# sch_LIMA_Driver.net
KiCad netlist of a schematic drawn in Altium Designer
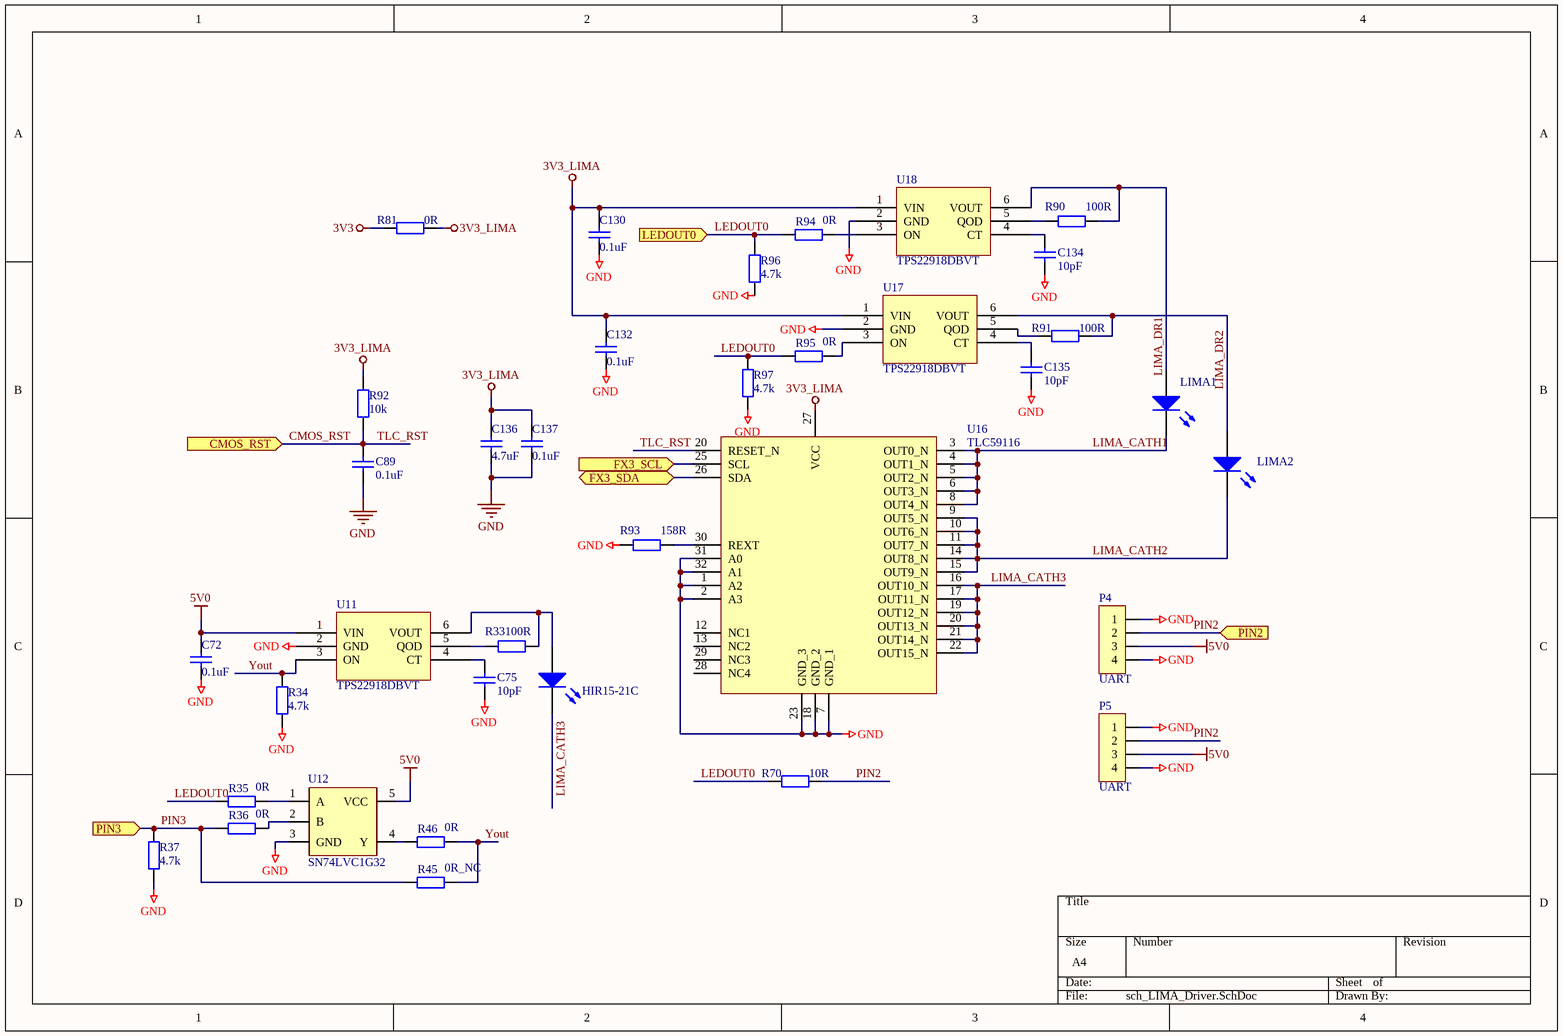
[diagram p0: sch_LIMA_Driver.SchDoc]

(export (version "E")
  (design (tool "Eeschema 10.0.6"))
  (components
    (comp (ref "C72")
      (value "0.1uF")
      (description "Capacitor")
      (fields (field (name "PUBLISHER") "Altium Limited"))
      (libsource (lib "Miscellaneous Devices") (part "Cap"))
    )
    (comp (ref "C75")
      (value "10pF")
      (footprint "0603C_N")
      (description "Capacitor")
      (fields (field (name "PUBLISHER") "Altium Limited"))
      (libsource (lib "Miscellaneous Devices") (part "Cap"))
    )
    (comp (ref "C89")
      (value "0.1uF")
      (footprint "0402C_L")
      (description "Capacitor")
      (fields (field (name "PUBLISHER") "Altium Limited"))
      (libsource (lib "Miscellaneous Devices") (part "Cap"))
    )
    (comp (ref "C130")
      (value "0.1uF")
      (footprint "0402C_L")
      (description "Capacitor")
      (fields (field (name "PUBLISHER") "Altium Limited"))
      (libsource (lib "Miscellaneous Devices") (part "Cap"))
    )
    (comp (ref "C132")
      (value "0.1uF")
      (footprint "0402C_L")
      (description "Capacitor")
      (fields (field (name "PUBLISHER") "Altium Limited"))
      (libsource (lib "Miscellaneous Devices") (part "Cap"))
    )
    (comp (ref "C134")
      (value "10pF")
      (footprint "0402C_L")
      (description "Capacitor")
      (fields (field (name "PUBLISHER") "Altium Limited"))
      (libsource (lib "Miscellaneous Devices") (part "Cap"))
    )
    (comp (ref "C135")
      (value "10pF")
      (footprint "0402C_L")
      (description "Capacitor")
      (fields (field (name "PUBLISHER") "Altium Limited"))
      (libsource (lib "Miscellaneous Devices") (part "Cap"))
    )
    (comp (ref "C136")
      (value "4.7uF")
      (description "Capacitor")
      (fields (field (name "PUBLISHER") "Altium Limited"))
      (libsource (lib "Miscellaneous Devices") (part "Cap"))
    )
    (comp (ref "C137")
      (value "0.1uF")
      (footprint "0402C")
      (description "Capacitor")
      (fields (field (name "PUBLISHER") "Altium Limited"))
      (libsource (lib "Miscellaneous Devices") (part "Cap"))
    )
    (comp (ref "HIR15-21C")
      (value "LIMA")
      (footprint "1206R")
      (description "发光二级管")
      (libsource (lib "TXW") (part "LED"))
    )
    (comp (ref "LIMA1") (value "LIMA") (description "发光二级管") (libsource (lib "TXW") (part "LED")))
    (comp (ref "LIMA2") (value "LIMA") (description "发光二级管") (libsource (lib "TXW") (part "LED")))
    (comp (ref "P4")
      (value "UART")
      (footprint "WAFER4_P1.25L6.25W3.4H4.3")
      (libsource (lib "KS_Drive") (part "CON4"))
    )
    (comp (ref "P5")
      (value "UART")
      (footprint "WAFER4_P1.25L6.25W3.4H4.3")
      (libsource (lib "KS_Drive") (part "CON4"))
    )
    (comp (ref "R33")
      (value "100R")
      (footprint "0603R_N")
      (description "Resistor")
      (fields (field (name "PUBLISHER") "Altium Limited"))
      (libsource (lib "SZG") (part "Resistor"))
    )
    (comp (ref "R34")
      (value "4.7k")
      (footprint "0603R_N")
      (description "Resistor")
      (fields (field (name "PUBLISHER") "Altium Limited"))
      (libsource (lib "") (part "Resistor_1"))
    )
    (comp (ref "R35")
      (value "0R")
      (footprint "0603R_N")
      (description "Resistor")
      (fields (field (name "PUBLISHER") "Altium Limited"))
      (libsource (lib "SZG") (part "Resistor"))
    )
    (comp (ref "R36")
      (value "0R")
      (footprint "0603R_N")
      (description "Resistor")
      (fields (field (name "PUBLISHER") "Altium Limited"))
      (libsource (lib "SZG") (part "Resistor"))
    )
    (comp (ref "R37")
      (value "4.7k")
      (footprint "0603R_N")
      (description "Resistor")
      (fields (field (name "PUBLISHER") "Altium Limited"))
      (libsource (lib "") (part "Resistor_1"))
    )
    (comp (ref "R45")
      (value "0R_NC")
      (footprint "0603R_N")
      (description "Resistor")
      (fields (field (name "PUBLISHER") "Altium Limited"))
      (libsource (lib "SZG") (part "Resistor"))
    )
    (comp (ref "R46")
      (value "0R")
      (footprint "0603R_N")
      (description "Resistor")
      (fields (field (name "PUBLISHER") "Altium Limited"))
      (libsource (lib "SZG") (part "Resistor"))
    )
    (comp (ref "R70")
      (value "10R")
      (footprint "0402R")
      (description "Resistor")
      (fields (field (name "PUBLISHER") "Altium Limited"))
      (libsource (lib "") (part "Resistor_2"))
    )
    (comp (ref "R81")
      (value "0R")
      (footprint "0402R")
      (description "Resistor")
      (fields (field (name "PUBLISHER") "Altium Limited"))
      (libsource (lib "") (part "Resistor_2"))
    )
    (comp (ref "R90")
      (value "100R")
      (footprint "0402R")
      (description "Resistor")
      (fields (field (name "PUBLISHER") "Altium Limited"))
      (libsource (lib "SZG") (part "Resistor"))
    )
    (comp (ref "R91")
      (value "100R")
      (footprint "0402R")
      (description "Resistor")
      (fields (field (name "PUBLISHER") "Altium Limited"))
      (libsource (lib "SZG") (part "Resistor"))
    )
    (comp (ref "R92")
      (value "10k")
      (footprint "0402R")
      (description "Resistor")
      (fields (field (name "PUBLISHER") "Altium Limited"))
      (libsource (lib "") (part "Resistor_3"))
    )
    (comp (ref "R93")
      (value "158R")
      (footprint "0402R")
      (description "Resistor")
      (fields (field (name "PUBLISHER") "Altium Limited"))
      (libsource (lib "SZG") (part "Resistor"))
    )
    (comp (ref "R94")
      (value "0R")
      (footprint "0402R")
      (description "Resistor")
      (fields (field (name "PUBLISHER") "Altium Limited"))
      (libsource (lib "SZG") (part "Resistor"))
    )
    (comp (ref "R95")
      (value "0R")
      (footprint "0402R")
      (description "Resistor")
      (fields (field (name "PUBLISHER") "Altium Limited"))
      (libsource (lib "SZG") (part "Resistor"))
    )
    (comp (ref "R96")
      (value "4.7k")
      (footprint "0402R")
      (description "Resistor")
      (fields (field (name "PUBLISHER") "Altium Limited"))
      (libsource (lib "") (part "Resistor_1"))
    )
    (comp (ref "R97")
      (value "4.7k")
      (footprint "0402R")
      (description "Resistor")
      (fields (field (name "PUBLISHER") "Altium Limited"))
      (libsource (lib "") (part "Resistor_1"))
    )
    (comp (ref "U11")
      (value "TPS22918DBVT")
      (footprint "SOT23-6_P0.95X2.4_L3W4.2H1.1")
      (libsource (lib "SZG") (part "TPS22918DBVT"))
    )
    (comp (ref "U12")
      (value "SN74LVC1G32")
      (footprint "SOT23-5_P0.95X2.4_L3W4.2H1.1")
      (libsource (lib "SZG") (part "SN74LVC1G32"))
    )
    (comp (ref "U16") (value "TLC59116") (libsource (lib "SZG") (part "TLC59116")))
    (comp (ref "U17") (value "TPS22918DBVT") (libsource (lib "SZG") (part "TPS22918DBVT")))
    (comp (ref "U18") (value "TPS22918DBVT") (libsource (lib "SZG") (part "TPS22918DBVT")))
  )
  (nets
    (net (code "1") (name "/CMOS_RST") (class "Default")
      (node (ref "C89") (pin "2") (pinfunction "2_2") (pintype "passive"))
      (node (ref "R92") (pin "2") (pinfunction "2_2") (pintype "passive"))
      (node (ref "U16") (pin "20") (pinfunction "RESET_N_20") (pintype "passive"))
    )
    (net (code "2") (name "/FX3_SCL") (class "Default")
      (node (ref "U16") (pin "25") (pinfunction "SCL_25") (pintype "passive"))
    )
    (net (code "3") (name "/FX3_SDA") (class "Default")
      (node (ref "U16") (pin "26") (pinfunction "SDA_26") (pintype "passive"))
    )
    (net (code "4") (name "/LEDOUT0") (class "Default")
      (node (ref "R35") (pin "2") (pinfunction "2_2") (pintype "passive"))
      (node (ref "R70") (pin "1") (pinfunction "1_1") (pintype "passive"))
      (node (ref "R94") (pin "2") (pinfunction "2_2") (pintype "passive"))
      (node (ref "R95") (pin "2") (pinfunction "2_2") (pintype "passive"))
      (node (ref "R96") (pin "2") (pinfunction "2_2") (pintype "passive"))
      (node (ref "R97") (pin "2") (pinfunction "2_2") (pintype "passive"))
    )
    (net (code "5") (name "/LIMA_CATH1") (class "Default")
      (node (ref "LIMA1") (pin "2") (pinfunction "K_2") (pintype "passive"))
      (node (ref "U16") (pin "3") (pinfunction "OUT0_N_3") (pintype "passive"))
      (node (ref "U16") (pin "4") (pinfunction "OUT1_N_4") (pintype "passive"))
      (node (ref "U16") (pin "5") (pinfunction "OUT2_N_5") (pintype "passive"))
      (node (ref "U16") (pin "6") (pinfunction "OUT3_N_6") (pintype "passive"))
      (node (ref "U16") (pin "8") (pinfunction "OUT4_N_8") (pintype "passive"))
    )
    (net (code "6") (name "/LIMA_CATH2") (class "Default")
      (node (ref "LIMA2") (pin "2") (pinfunction "K_2") (pintype "passive"))
      (node (ref "U16") (pin "10") (pinfunction "OUT6_N_10") (pintype "passive"))
      (node (ref "U16") (pin "11") (pinfunction "OUT7_N_11") (pintype "passive"))
      (node (ref "U16") (pin "14") (pinfunction "OUT8_N_14") (pintype "passive"))
      (node (ref "U16") (pin "15") (pinfunction "OUT9_N_15") (pintype "passive"))
      (node (ref "U16") (pin "9") (pinfunction "OUT5_N_9") (pintype "passive"))
    )
    (net (code "7") (name "/LIMA_CATH3") (class "Default")
      (node (ref "HIR15-21C") (pin "2") (pinfunction "K_2") (pintype "passive"))
      (node (ref "U16") (pin "16") (pinfunction "OUT10_N_16") (pintype "passive"))
      (node (ref "U16") (pin "17") (pinfunction "OUT11_N_17") (pintype "passive"))
      (node (ref "U16") (pin "19") (pinfunction "OUT12_N_19") (pintype "passive"))
      (node (ref "U16") (pin "20") (pinfunction "OUT13_N_20") (pintype "passive"))
      (node (ref "U16") (pin "21") (pinfunction "OUT14_N_21") (pintype "passive"))
      (node (ref "U16") (pin "22") (pinfunction "OUT15_N_22") (pintype "passive"))
    )
    (net (code "9") (name "/LIMA_DR2") (class "Default")
      (node (ref "LIMA2") (pin "1") (pinfunction "A_1") (pintype "passive"))
      (node (ref "R91") (pin "1") (pinfunction "1_1") (pintype "passive"))
      (node (ref "U17") (pin "6") (pinfunction "VOUT_6") (pintype "passive"))
    )
    (net (code "10") (name "/PIN2") (class "Default")
      (node (ref "P4") (pin "2") (pinfunction "2_2") (pintype "passive"))
      (node (ref "P5") (pin "2") (pinfunction "2_2") (pintype "passive"))
      (node (ref "R70") (pin "2") (pinfunction "2_2") (pintype "passive"))
    )
    (net (code "11") (name "/PIN3") (class "Default")
      (node (ref "R36") (pin "2") (pinfunction "2_2") (pintype "passive"))
      (node (ref "R37") (pin "2") (pinfunction "2_2") (pintype "passive"))
      (node (ref "R45") (pin "2") (pinfunction "2_2") (pintype "passive"))
    )
    (net (code "12") (name "/Yout") (class "Default")
      (node (ref "R34") (pin "2") (pinfunction "2_2") (pintype "passive"))
      (node (ref "R45") (pin "1") (pinfunction "1_1") (pintype "passive"))
      (node (ref "R46") (pin "1") (pinfunction "1_1") (pintype "passive"))
      (node (ref "U11") (pin "3") (pinfunction "ON_3") (pintype "passive"))
    )
    (net (code "13") (name "3V3") (class "Default")
      (node (ref "R81") (pin "1") (pinfunction "1_1") (pintype "passive"))
    )
    (net (code "14") (name "3V3_LIMA") (class "Default")
      (node (ref "C130") (pin "2") (pinfunction "2_2") (pintype "passive"))
      (node (ref "C132") (pin "2") (pinfunction "2_2") (pintype "passive"))
      (node (ref "C136") (pin "2") (pinfunction "2_2") (pintype "passive"))
      (node (ref "C137") (pin "2") (pinfunction "2_2") (pintype "passive"))
      (node (ref "R81") (pin "2") (pinfunction "2_2") (pintype "passive"))
      (node (ref "R92") (pin "1") (pinfunction "1_1") (pintype "passive"))
      (node (ref "U16") (pin "27") (pinfunction "VCC_27") (pintype "passive"))
      (node (ref "U17") (pin "1") (pinfunction "VIN_1") (pintype "passive"))
      (node (ref "U18") (pin "1") (pinfunction "VIN_1") (pintype "passive"))
    )
    (net (code "15") (name "5V0") (class "Default")
      (node (ref "C72") (pin "2") (pinfunction "2_2") (pintype "passive"))
      (node (ref "P4") (pin "3") (pinfunction "3_3") (pintype "passive"))
      (node (ref "P5") (pin "3") (pinfunction "3_3") (pintype "passive"))
      (node (ref "U11") (pin "1") (pinfunction "VIN_1") (pintype "passive"))
      (node (ref "U12") (pin "5") (pinfunction "VCC_5") (pintype "passive"))
    )
    (net (code "16") (name "GND") (class "Default")
      (node (ref "C130") (pin "1") (pinfunction "1_1") (pintype "passive"))
      (node (ref "C132") (pin "1") (pinfunction "1_1") (pintype "passive"))
      (node (ref "C134") (pin "1") (pinfunction "1_1") (pintype "passive"))
      (node (ref "C135") (pin "1") (pinfunction "1_1") (pintype "passive"))
      (node (ref "C136") (pin "1") (pinfunction "1_1") (pintype "passive"))
      (node (ref "C137") (pin "1") (pinfunction "1_1") (pintype "passive"))
      (node (ref "C72") (pin "1") (pinfunction "1_1") (pintype "passive"))
      (node (ref "C75") (pin "1") (pinfunction "1_1") (pintype "passive"))
      (node (ref "C89") (pin "1") (pinfunction "1_1") (pintype "passive"))
      (node (ref "P4") (pin "1") (pinfunction "1_1") (pintype "passive"))
      (node (ref "P4") (pin "4") (pinfunction "4_4") (pintype "passive"))
      (node (ref "P5") (pin "1") (pinfunction "1_1") (pintype "passive"))
      (node (ref "P5") (pin "4") (pinfunction "4_4") (pintype "passive"))
      (node (ref "R34") (pin "1") (pinfunction "1_1") (pintype "passive"))
      (node (ref "R37") (pin "1") (pinfunction "1_1") (pintype "passive"))
      (node (ref "R93") (pin "2") (pinfunction "2_2") (pintype "passive"))
      (node (ref "R96") (pin "1") (pinfunction "1_1") (pintype "passive"))
      (node (ref "R97") (pin "1") (pinfunction "1_1") (pintype "passive"))
      (node (ref "U11") (pin "2") (pinfunction "GND_2") (pintype "passive"))
      (node (ref "U12") (pin "3") (pinfunction "GND_3") (pintype "passive"))
      (node (ref "U16") (pin "1") (pinfunction "A2_1") (pintype "passive"))
      (node (ref "U16") (pin "18") (pinfunction "GND_2_18") (pintype "passive"))
      (node (ref "U16") (pin "2") (pinfunction "A3_2") (pintype "passive"))
      (node (ref "U16") (pin "23") (pinfunction "GND_3_23") (pintype "passive"))
      (node (ref "U16") (pin "31") (pinfunction "A0_31") (pintype "passive"))
      (node (ref "U16") (pin "32") (pinfunction "A1_32") (pintype "passive"))
      (node (ref "U16") (pin "7") (pinfunction "GND_1_7") (pintype "passive"))
      (node (ref "U17") (pin "2") (pinfunction "GND_2") (pintype "passive"))
      (node (ref "U18") (pin "2") (pinfunction "GND_2") (pintype "passive"))
    )
    (net (code "17") (name "Net-(HIR15-21C-A)") (class "Default")
      (node (ref "HIR15-21C") (pin "1") (pinfunction "A_1") (pintype "passive"))
      (node (ref "R33") (pin "1") (pinfunction "1_1") (pintype "passive"))
      (node (ref "U11") (pin "6") (pinfunction "VOUT_6") (pintype "passive"))
    )
    (net (code "18") (name "Net-(LIMA1-A)") (class "Default")
      (node (ref "LIMA1") (pin "1") (pinfunction "A_1") (pintype "passive"))
      (node (ref "R90") (pin "1") (pinfunction "1_1") (pintype "passive"))
      (node (ref "U18") (pin "6") (pinfunction "VOUT_6") (pintype "passive"))
    )
    (net (code "19") (name "Net-(U11-CT)") (class "Default")
      (node (ref "C75") (pin "2") (pinfunction "2_2") (pintype "passive"))
      (node (ref "U11") (pin "4") (pinfunction "CT_4") (pintype "passive"))
    )
    (net (code "20") (name "Net-(U11-QOD)") (class "Default")
      (node (ref "R33") (pin "2") (pinfunction "2_2") (pintype "passive"))
      (node (ref "U11") (pin "5") (pinfunction "QOD_5") (pintype "passive"))
    )
    (net (code "21") (name "Net-(U12-A)") (class "Default")
      (node (ref "R35") (pin "1") (pinfunction "1_1") (pintype "passive"))
      (node (ref "U12") (pin "1") (pinfunction "A_1") (pintype "passive"))
    )
    (net (code "22") (name "Net-(U12-B)") (class "Default")
      (node (ref "R36") (pin "1") (pinfunction "1_1") (pintype "passive"))
      (node (ref "U12") (pin "2") (pinfunction "B_2") (pintype "passive"))
    )
    (net (code "23") (name "Net-(U12-Y)") (class "Default")
      (node (ref "R46") (pin "2") (pinfunction "2_2") (pintype "passive"))
      (node (ref "U12") (pin "4") (pinfunction "Y_4") (pintype "passive"))
    )
    (net (code "24") (name "Net-(U16-REXT)") (class "Default")
      (node (ref "R93") (pin "1") (pinfunction "1_1") (pintype "passive"))
      (node (ref "U16") (pin "30") (pinfunction "REXT_30") (pintype "passive"))
    )
    (net (code "25") (name "Net-(U17-CT)") (class "Default")
      (node (ref "C135") (pin "2") (pinfunction "2_2") (pintype "passive"))
      (node (ref "U17") (pin "4") (pinfunction "CT_4") (pintype "passive"))
    )
    (net (code "26") (name "Net-(U17-ON)") (class "Default")
      (node (ref "R95") (pin "1") (pinfunction "1_1") (pintype "passive"))
      (node (ref "U17") (pin "3") (pinfunction "ON_3") (pintype "passive"))
    )
    (net (code "27") (name "Net-(U17-QOD)") (class "Default")
      (node (ref "R91") (pin "2") (pinfunction "2_2") (pintype "passive"))
      (node (ref "U17") (pin "5") (pinfunction "QOD_5") (pintype "passive"))
    )
    (net (code "28") (name "Net-(U18-CT)") (class "Default")
      (node (ref "C134") (pin "2") (pinfunction "2_2") (pintype "passive"))
      (node (ref "U18") (pin "4") (pinfunction "CT_4") (pintype "passive"))
    )
    (net (code "29") (name "Net-(U18-ON)") (class "Default")
      (node (ref "R94") (pin "1") (pinfunction "1_1") (pintype "passive"))
      (node (ref "U18") (pin "3") (pinfunction "ON_3") (pintype "passive"))
    )
    (net (code "30") (name "Net-(U18-QOD)") (class "Default")
      (node (ref "R90") (pin "2") (pinfunction "2_2") (pintype "passive"))
      (node (ref "U18") (pin "5") (pinfunction "QOD_5") (pintype "passive"))
    )
    (net (code "31") (name "unconnected-(U16-NC1-Pad12)") (class "Default")
      (node (ref "U16") (pin "12") (pinfunction "NC1_12") (pintype "passive"))
    )
    (net (code "32") (name "unconnected-(U16-NC2-Pad13)") (class "Default")
      (node (ref "U16") (pin "13") (pinfunction "NC2_13") (pintype "passive"))
    )
    (net (code "33") (name "unconnected-(U16-NC3-Pad29)") (class "Default")
      (node (ref "U16") (pin "29") (pinfunction "NC3_29") (pintype "passive"))
    )
    (net (code "34") (name "unconnected-(U16-NC4-Pad28)") (class "Default")
      (node (ref "U16") (pin "28") (pinfunction "NC4_28") (pintype "passive"))
    )
  )
)
